# 1.net
KiCad netlist of a schematic drawn in Altium Designer
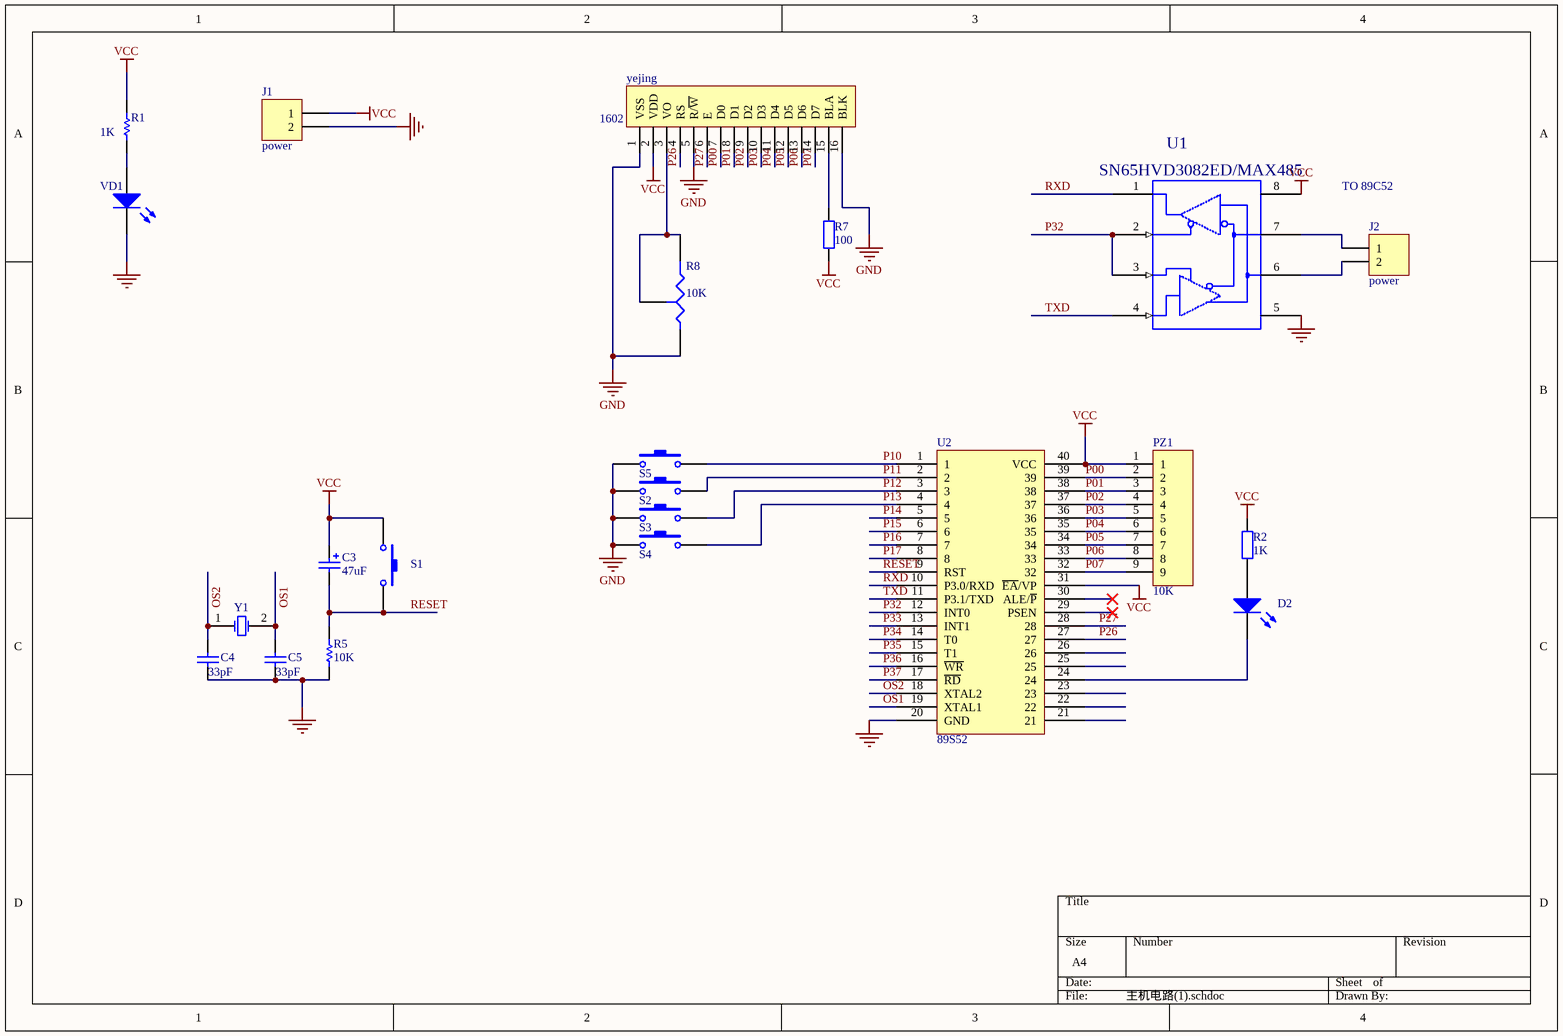
[diagram p0: 主机电路(1).schdoc]

(export (version "E")
  (design (tool "Eeschema 10.0.6"))
  (components
    (comp (ref "C3")
      (value "47uF")
      (footprint "B")
      (description "Polarized Capacitor (Axial)")
      (fields (field (name "Comment") "4.7uF") (field (name "PUBLISHER") "Altium Limited"))
      (libsource (lib "*") (part "Cap Pol2"))
    )
    (comp (ref "C4")
      (value "33pF")
      (footprint "HDR1X2")
      (description "Capacitor")
      (fields (field (name "Comment") "20P") (field (name "PUBLISHER") "Altium Limited"))
      (libsource (lib "*") (part "Cap"))
    )
    (comp (ref "C5")
      (value "33pF")
      (footprint "HDR1X2")
      (description "Capacitor")
      (fields (field (name "Comment") "20P") (field (name "PUBLISHER") "Altium Limited"))
      (libsource (lib "*") (part "Cap"))
    )
    (comp (ref "D2")
      (value "LED0")
      (footprint "LED")
      (description "Typical INFRARED GaAs LED")
      (fields (field (name "PUBLISHER") "Altium Limited"))
      (libsource (lib "Miscellaneous Devices") (part "LED0"))
    )
    (comp (ref "J1")
      (value "power")
      (footprint "DC-5mm")
      (description "Header, 2-Pin")
      (fields (field (name "PUBLISHER") "Altium Limited"))
      (libsource (lib "*") (part "Header 2"))
    )
    (comp (ref "J2")
      (value "power")
      (footprint "HDR1X2")
      (description "Header, 2-Pin")
      (fields (field (name "PUBLISHER") "Altium Limited"))
      (libsource (lib "") (part "Header 2_1"))
    )
    (comp (ref "PZ1")
      (value "paizu")
      (footprint "HDR1X9")
      (fields (field (name "ALTIUM_UNNAMED_1") "10K"))
      (libsource (lib "*") (part "pai zu"))
    )
    (comp (ref "R1")
      (value "1K")
      (footprint "res")
      (description "Resistor")
      (fields (field (name "PUBLISHER") "Altium Limited"))
      (libsource (lib "*") (part "Res1"))
    )
    (comp (ref "R2")
      (value "1K")
      (footprint "res")
      (description "Resistor")
      (fields (field (name "PUBLISHER") "Altium Limited"))
      (libsource (lib "Miscellaneous Devices") (part "Res2"))
    )
    (comp (ref "R5")
      (value "10K")
      (footprint "AXIAL-0.4")
      (description "Resistor")
      (fields (field (name "PUBLISHER") "Altium Limited"))
      (libsource (lib "*") (part "Res1"))
    )
    (comp (ref "R7")
      (value "100")
      (footprint "res")
      (description "Resistor")
      (fields (field (name "Comment") "Res2") (field (name "PUBLISHER") "Altium Limited"))
      (libsource (lib "") (part "Res2_1"))
    )
    (comp (ref "R8")
      (value "10K")
      (footprint "xtal2")
      (description "Tapped Resistor")
      (fields (field (name "Comment") "Res Tap") (field (name "PUBLISHER") "Altium Limited"))
      (libsource (lib "Miscellaneous Devices") (part "Res Tap"))
    )
    (comp (ref "S1")
      (value "SW-PB")
      (footprint "sw")
      (description "Switch")
      (fields (field (name "PUBLISHER") "Altium Limited"))
      (libsource (lib "*") (part "SW-PB"))
    )
    (comp (ref "S2")
      (value "SW-PB")
      (footprint "sw")
      (description "Switch")
      (fields (field (name "PUBLISHER") "Altium Limited"))
      (libsource (lib "*") (part "SW-PB"))
    )
    (comp (ref "S3")
      (value "SW-PB")
      (footprint "sw")
      (description "Switch")
      (fields (field (name "PUBLISHER") "Altium Limited"))
      (libsource (lib "*") (part "SW-PB"))
    )
    (comp (ref "S4")
      (value "SW-PB")
      (footprint "sw")
      (description "Switch")
      (fields (field (name "PUBLISHER") "Altium Limited"))
      (libsource (lib "*") (part "SW-PB"))
    )
    (comp (ref "S5")
      (value "SW-PB")
      (footprint "sw")
      (description "Switch")
      (fields (field (name "PUBLISHER") "Altium Limited"))
      (libsource (lib "*") (part "SW-PB"))
    )
    (comp (ref "U1")
      (value "SN65HVD3082ED/MAX485")
      (footprint "DIP8")
      (libsource (lib "*") (part "Pro3052.TMP_75176_22"))
    )
    (comp (ref "U2") (value "89S52") (footprint "DIP40") (libsource (lib "*") (part "89S52")))
    (comp (ref "VD1")
      (value "LED0")
      (footprint "led")
      (description "Typical INFRARED GaAs LED")
      (fields (field (name "PUBLISHER") "Altium Limited"))
      (libsource (lib "*") (part "LED0"))
    )
    (comp (ref "Y1")
      (value "12MHz")
      (footprint "晶振 22.1184")
      (description "Crystal Oscillator")
      (fields (field (name "PUBLISHER") "Altium Limited"))
      (libsource (lib "*") (part "XTAL"))
    )
    (comp (ref "yejing") (value "1602") (footprint "1602液晶") (libsource (lib "元件库") (part "1602")))
  )
  (nets
    (net (code "1") (name "/OS1") (class "Default")
      (node (ref "C5") (pin "2") (pinfunction "2_2") (pintype "passive"))
      (node (ref "U2") (pin "19") (pinfunction "XTAL1_19") (pintype "passive"))
      (node (ref "Y1") (pin "2") (pinfunction "OSC2_2") (pintype "passive"))
    )
    (net (code "2") (name "/OS2") (class "Default")
      (node (ref "C4") (pin "2") (pinfunction "2_2") (pintype "passive"))
      (node (ref "U2") (pin "18") (pinfunction "XTAL2_18") (pintype "passive"))
      (node (ref "Y1") (pin "1") (pinfunction "OSC1_1") (pintype "passive"))
    )
    (net (code "3") (name "/P00") (class "Default")
      (node (ref "PZ1") (pin "2") (pinfunction "2_2") (pintype "passive"))
      (node (ref "U2") (pin "39") (pinfunction "39_39") (pintype "passive"))
      (node (ref "yejing") (pin "7") (pinfunction "D0_7") (pintype "passive"))
    )
    (net (code "4") (name "/P01") (class "Default")
      (node (ref "PZ1") (pin "3") (pinfunction "3_3") (pintype "passive"))
      (node (ref "U2") (pin "38") (pinfunction "38_38") (pintype "passive"))
      (node (ref "yejing") (pin "8") (pinfunction "D1_8") (pintype "passive"))
    )
    (net (code "5") (name "/P02") (class "Default")
      (node (ref "PZ1") (pin "4") (pinfunction "4_4") (pintype "passive"))
      (node (ref "U2") (pin "37") (pinfunction "37_37") (pintype "passive"))
      (node (ref "yejing") (pin "9") (pinfunction "D2_9") (pintype "passive"))
    )
    (net (code "6") (name "/P03") (class "Default")
      (node (ref "PZ1") (pin "5") (pinfunction "5_5") (pintype "passive"))
      (node (ref "U2") (pin "36") (pinfunction "36_36") (pintype "passive"))
      (node (ref "yejing") (pin "10") (pinfunction "D3_10") (pintype "passive"))
    )
    (net (code "7") (name "/P04") (class "Default")
      (node (ref "PZ1") (pin "6") (pinfunction "6_6") (pintype "passive"))
      (node (ref "U2") (pin "35") (pinfunction "35_35") (pintype "passive"))
      (node (ref "yejing") (pin "11") (pinfunction "D4_11") (pintype "passive"))
    )
    (net (code "8") (name "/P05") (class "Default")
      (node (ref "PZ1") (pin "7") (pinfunction "7_7") (pintype "passive"))
      (node (ref "U2") (pin "34") (pinfunction "34_34") (pintype "passive"))
      (node (ref "yejing") (pin "12") (pinfunction "D5_12") (pintype "passive"))
    )
    (net (code "9") (name "/P06") (class "Default")
      (node (ref "PZ1") (pin "8") (pinfunction "8_8") (pintype "passive"))
      (node (ref "U2") (pin "33") (pinfunction "33_33") (pintype "passive"))
      (node (ref "yejing") (pin "13") (pinfunction "D6_13") (pintype "passive"))
    )
    (net (code "10") (name "/P07") (class "Default")
      (node (ref "PZ1") (pin "9") (pinfunction "9_9") (pintype "passive"))
      (node (ref "U2") (pin "32") (pinfunction "32_32") (pintype "passive"))
      (node (ref "yejing") (pin "14") (pinfunction "D7_14") (pintype "passive"))
    )
    (net (code "11") (name "/P10") (class "Default")
      (node (ref "S5") (pin "2") (pinfunction "2_2") (pintype "passive"))
      (node (ref "U2") (pin "1") (pinfunction "1_1") (pintype "passive"))
    )
    (net (code "12") (name "/P11") (class "Default")
      (node (ref "S2") (pin "2") (pinfunction "2_2") (pintype "passive"))
      (node (ref "U2") (pin "2") (pinfunction "2_2") (pintype "passive"))
    )
    (net (code "13") (name "/P12") (class "Default")
      (node (ref "S3") (pin "2") (pinfunction "2_2") (pintype "passive"))
      (node (ref "U2") (pin "3") (pinfunction "3_3") (pintype "passive"))
    )
    (net (code "14") (name "/P13") (class "Default")
      (node (ref "S4") (pin "2") (pinfunction "2_2") (pintype "passive"))
      (node (ref "U2") (pin "4") (pinfunction "4_4") (pintype "passive"))
    )
    (net (code "15") (name "/P14") (class "Default")
      (node (ref "U2") (pin "5") (pinfunction "5_5") (pintype "passive"))
    )
    (net (code "16") (name "/P15") (class "Default")
      (node (ref "U2") (pin "6") (pinfunction "6_6") (pintype "passive"))
    )
    (net (code "17") (name "/P16") (class "Default")
      (node (ref "U2") (pin "7") (pinfunction "7_7") (pintype "passive"))
    )
    (net (code "18") (name "/P17") (class "Default")
      (node (ref "U2") (pin "8") (pinfunction "8_8") (pintype "passive"))
    )
    (net (code "19") (name "/P26") (class "Default")
      (node (ref "U2") (pin "27") (pinfunction "27_27") (pintype "passive"))
      (node (ref "yejing") (pin "4") (pinfunction "RS_4") (pintype "passive"))
    )
    (net (code "20") (name "/P27") (class "Default")
      (node (ref "U2") (pin "28") (pinfunction "28_28") (pintype "passive"))
      (node (ref "yejing") (pin "6") (pinfunction "E_6") (pintype "passive"))
    )
    (net (code "21") (name "/P32") (class "Default")
      (node (ref "U1") (pin "2") (pintype "input"))
      (node (ref "U1") (pin "3") (pintype "input"))
      (node (ref "U2") (pin "12") (pinfunction "INT0_12") (pintype "passive"))
    )
    (net (code "22") (name "/P33") (class "Default")
      (node (ref "U2") (pin "13") (pinfunction "INT1_13") (pintype "passive"))
    )
    (net (code "23") (name "/P34") (class "Default")
      (node (ref "U2") (pin "14") (pinfunction "T0_14") (pintype "passive"))
    )
    (net (code "24") (name "/P35") (class "Default")
      (node (ref "U2") (pin "15") (pinfunction "T1_15") (pintype "passive"))
    )
    (net (code "25") (name "/P36") (class "Default")
      (node (ref "U2") (pin "16") (pinfunction "~{WR}_16") (pintype "passive"))
    )
    (net (code "26") (name "/P37") (class "Default")
      (node (ref "U2") (pin "17") (pinfunction "~{RD}_17") (pintype "passive"))
    )
    (net (code "27") (name "/RESET") (class "Default")
      (node (ref "C3") (pin "2") (pinfunction "1_2") (pintype "passive"))
      (node (ref "R5") (pin "2") (pinfunction "2_2") (pintype "passive"))
      (node (ref "S1") (pin "2") (pinfunction "2_2") (pintype "passive"))
      (node (ref "U2") (pin "9") (pinfunction "RST_9") (pintype "passive"))
    )
    (net (code "28") (name "/RXD") (class "Default")
      (node (ref "U1") (pin "1") (pintype "passive"))
      (node (ref "U2") (pin "10") (pinfunction "P3.0/RXD_10") (pintype "passive"))
    )
    (net (code "29") (name "/TXD") (class "Default")
      (node (ref "U1") (pin "4") (pintype "input"))
      (node (ref "U2") (pin "11") (pinfunction "P3.1/TXD_11") (pintype "passive"))
    )
    (net (code "30") (name "GND") (class "Default")
      (node (ref "C4") (pin "1") (pinfunction "1_1") (pintype "passive"))
      (node (ref "C5") (pin "1") (pinfunction "1_1") (pintype "passive"))
      (node (ref "J1") (pin "2") (pinfunction "2_2") (pintype "passive"))
      (node (ref "R5") (pin "1") (pinfunction "1_1") (pintype "passive"))
      (node (ref "R8") (pin "1") (pinfunction "A_1") (pintype "passive"))
      (node (ref "S2") (pin "1") (pinfunction "1_1") (pintype "passive"))
      (node (ref "S3") (pin "1") (pinfunction "1_1") (pintype "passive"))
      (node (ref "S4") (pin "1") (pinfunction "1_1") (pintype "passive"))
      (node (ref "S5") (pin "1") (pinfunction "1_1") (pintype "passive"))
      (node (ref "U1") (pin "5") (pinfunction "GND_5") (pintype "passive"))
      (node (ref "U2") (pin "20") (pinfunction "GND_20") (pintype "passive"))
      (node (ref "VD1") (pin "1") (pinfunction "A_1") (pintype "passive"))
      (node (ref "yejing") (pin "1") (pinfunction "VSS_1") (pintype "passive"))
      (node (ref "yejing") (pin "16") (pinfunction "BLK_16") (pintype "passive"))
      (node (ref "yejing") (pin "5") (pinfunction "R/~{W}_5") (pintype "passive"))
    )
    (net (code "31") (name "Net-(D2-A)") (class "Default")
      (node (ref "D2") (pin "1") (pinfunction "A_1") (pintype "passive"))
      (node (ref "R2") (pin "2") (pinfunction "2_2") (pintype "passive"))
    )
    (net (code "32") (name "Net-(D2-K)") (class "Default")
      (node (ref "D2") (pin "2") (pinfunction "K_2") (pintype "passive"))
      (node (ref "U2") (pin "24") (pinfunction "24_24") (pintype "passive"))
    )
    (net (code "33") (name "Net-(J2-Pad1)") (class "Default")
      (node (ref "J2") (pin "1") (pinfunction "1_1") (pintype "passive"))
      (node (ref "U1") (pin "7") (pintype "tri_state"))
    )
    (net (code "34") (name "Net-(J2-Pad2)") (class "Default")
      (node (ref "J2") (pin "2") (pinfunction "2_2") (pintype "passive"))
      (node (ref "U1") (pin "6") (pintype "tri_state"))
    )
    (net (code "35") (name "Net-(R8-B)") (class "Default")
      (node (ref "R8") (pin "2") (pinfunction "B_2") (pintype "passive"))
      (node (ref "R8") (pin "3") (pinfunction "TAP_3") (pintype "passive"))
      (node (ref "yejing") (pin "3") (pinfunction "VO_3") (pintype "passive"))
    )
    (net (code "36") (name "Net-(VD1-K)") (class "Default")
      (node (ref "R1") (pin "1") (pinfunction "1_1") (pintype "passive"))
      (node (ref "VD1") (pin "2") (pinfunction "K_2") (pintype "passive"))
    )
    (net (code "37") (name "Net-(yejing-BLA)") (class "Default")
      (node (ref "R7") (pin "2") (pinfunction "2_2") (pintype "passive"))
      (node (ref "yejing") (pin "15") (pinfunction "BLA_15") (pintype "passive"))
    )
    (net (code "38") (name "VCC") (class "Default")
      (node (ref "C3") (pin "1") (pinfunction "2_1") (pintype "passive"))
      (node (ref "J1") (pin "1") (pinfunction "1_1") (pintype "passive"))
      (node (ref "PZ1") (pin "1") (pinfunction "1_1") (pintype "passive"))
      (node (ref "R1") (pin "2") (pinfunction "2_2") (pintype "passive"))
      (node (ref "R2") (pin "1") (pinfunction "1_1") (pintype "passive"))
      (node (ref "R7") (pin "1") (pinfunction "1_1") (pintype "passive"))
      (node (ref "S1") (pin "1") (pinfunction "1_1") (pintype "passive"))
      (node (ref "U1") (pin "8") (pinfunction "VCC_8") (pintype "power_in"))
      (node (ref "U2") (pin "31") (pinfunction "~{EA}/VP_31") (pintype "passive"))
      (node (ref "U2") (pin "40") (pinfunction "VCC_40") (pintype "passive"))
      (node (ref "yejing") (pin "2") (pinfunction "VDD_2") (pintype "passive"))
    )
    (net (code "39") (name "unconnected-(U2-ALE{slash}~{P}-Pad30)") (class "Default")
      (node (ref "U2") (pin "30") (pinfunction "ALE/~{P}_30") (pintype "passive+no_connect"))
    )
    (net (code "40") (name "unconnected-(U2-PSEN-Pad29)") (class "Default")
      (node (ref "U2") (pin "29") (pinfunction "PSEN_29") (pintype "passive+no_connect"))
    )
    (net (code "41") (name "unconnected-(U2-Pad21)") (class "Default")
      (node (ref "U2") (pin "21") (pinfunction "21_21") (pintype "passive"))
    )
    (net (code "42") (name "unconnected-(U2-Pad22)") (class "Default")
      (node (ref "U2") (pin "22") (pinfunction "22_22") (pintype "passive"))
    )
    (net (code "43") (name "unconnected-(U2-Pad23)") (class "Default")
      (node (ref "U2") (pin "23") (pinfunction "23_23") (pintype "passive"))
    )
    (net (code "44") (name "unconnected-(U2-Pad25)") (class "Default")
      (node (ref "U2") (pin "25") (pinfunction "25_25") (pintype "passive"))
    )
    (net (code "45") (name "unconnected-(U2-Pad26)") (class "Default")
      (node (ref "U2") (pin "26") (pinfunction "26_26") (pintype "passive"))
    )
  )
)
